# rat.net
KiCad netlist of a schematic drawn in EAGLE
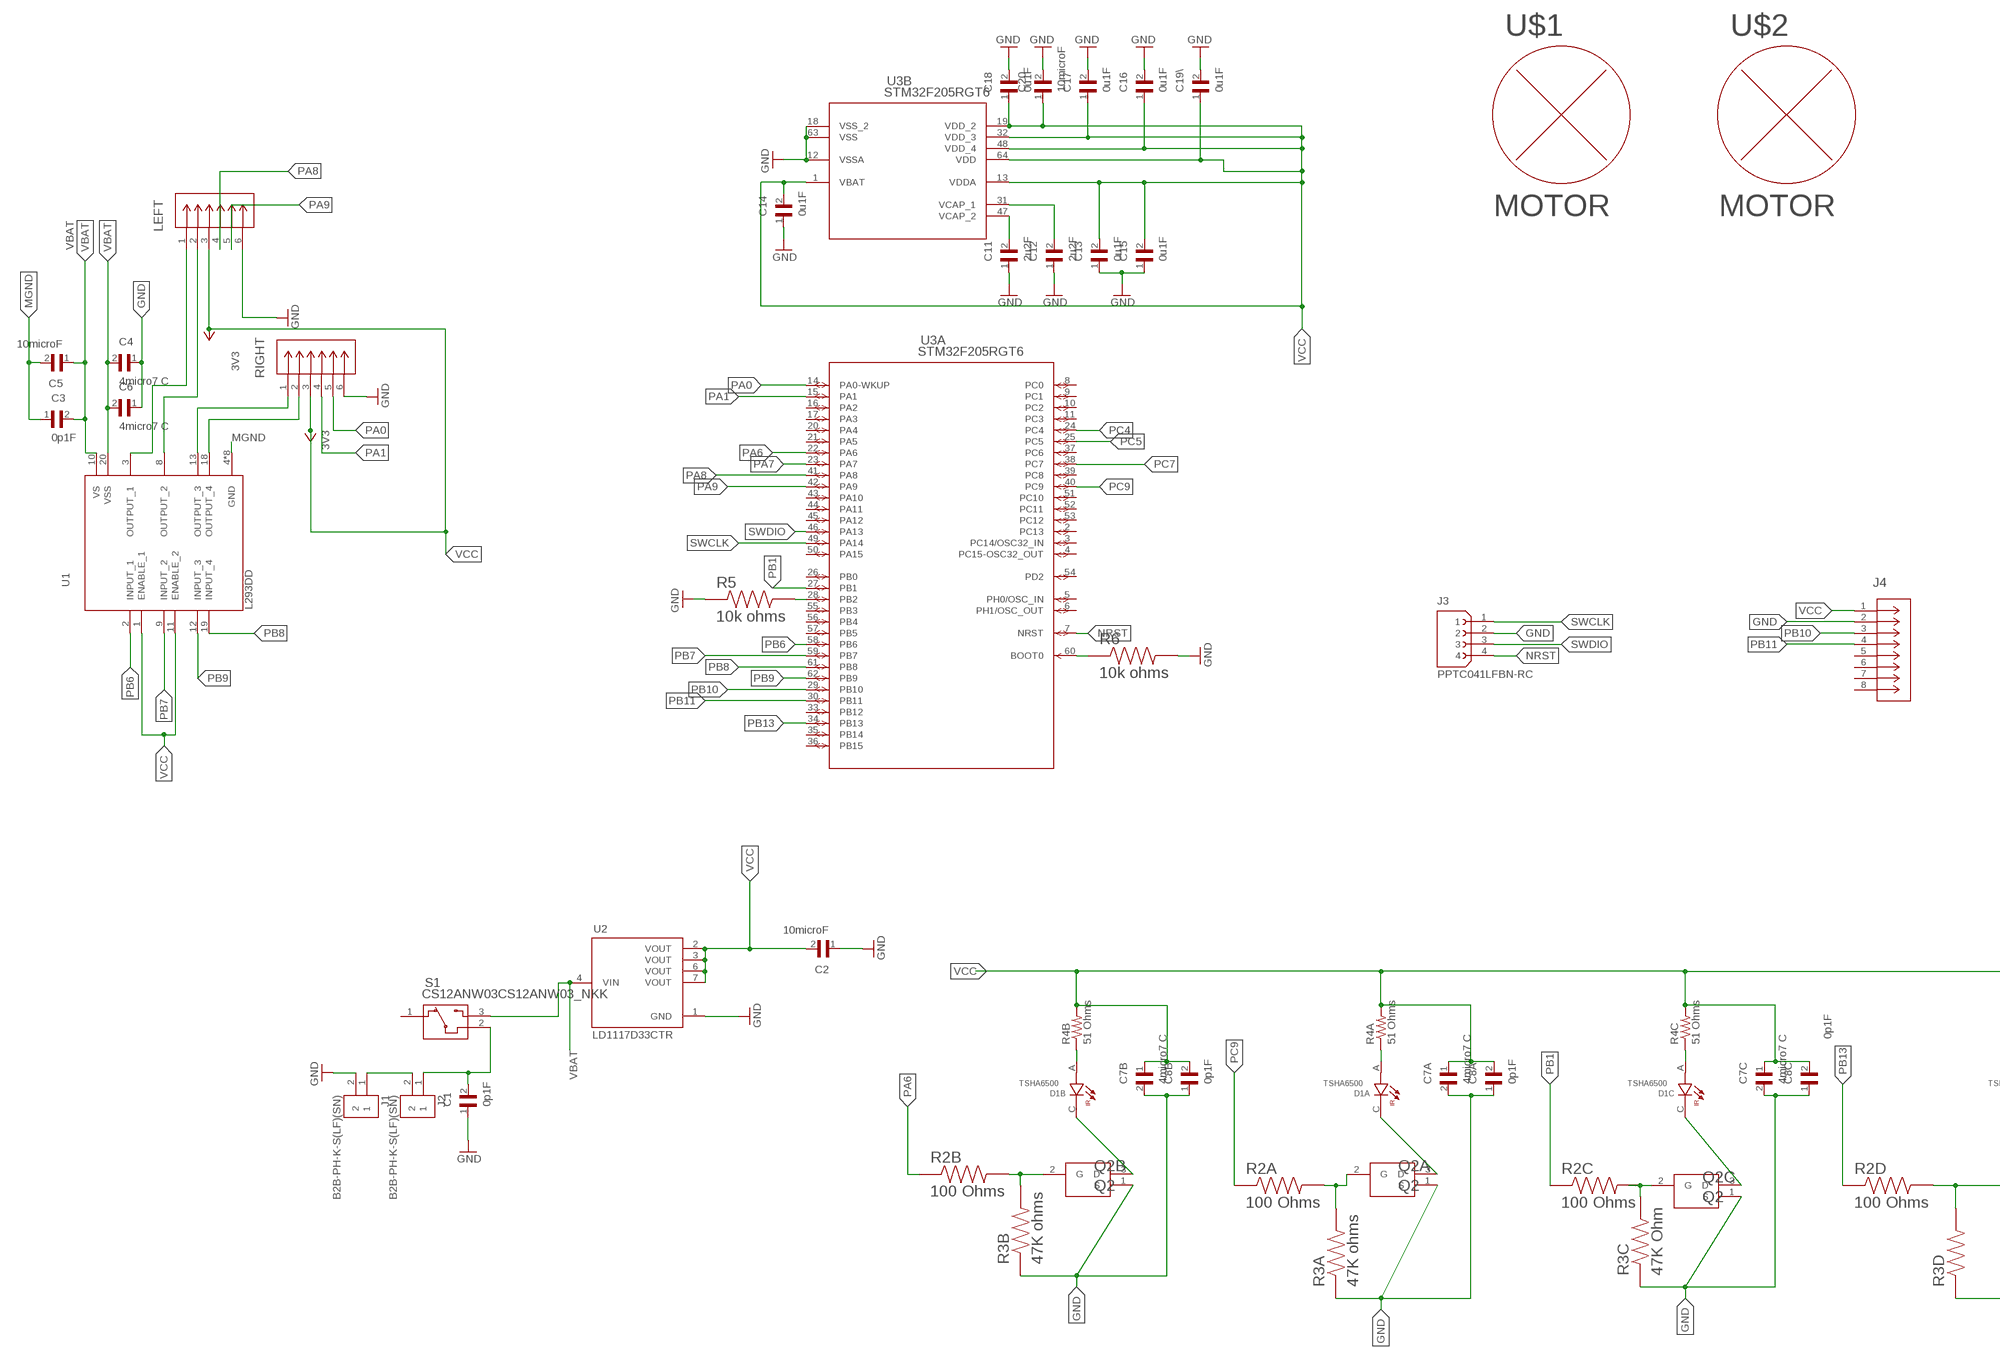
[diagram p0: schematic, sheet 1, part 1 of 2]
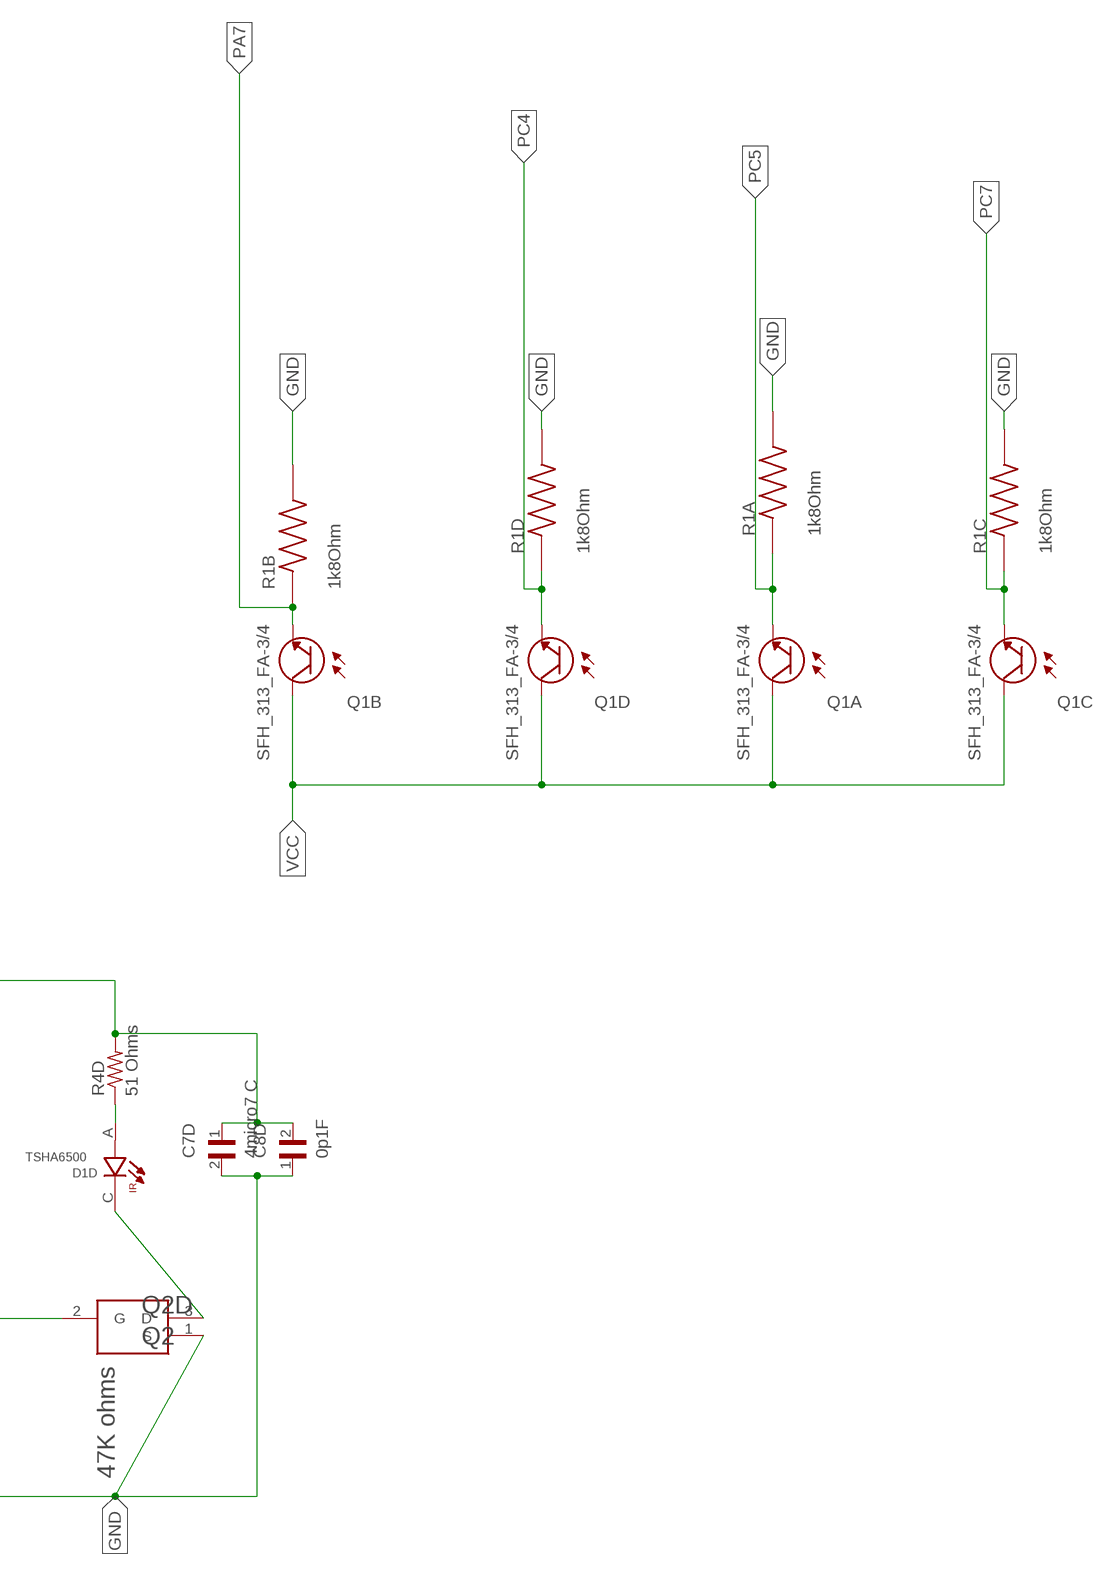
[diagram p1: schematic, sheet 1, part 2 of 2]

(export (version "E")
  (design (tool "Eeschema 10.0.6"))
  (components
    (comp (ref "C1")
      (value "0p1F")
      (footprint "eagle-import:CAPC3216X94N")
      (fields
        (field (name "DIGI-KEY_PART_NUMBER") "478-12514-1-ND")
        (field (name "MF") "AVX")
        (field (name "MP") "12065C104JAT4A")
      )
      (libsource (lib "eagle-import") (part "12065C104JAT4A"))
    )
    (comp (ref "C2")
      (value "10microF")
      (footprint "eagle-import:CAPC2012X145N")
      (fields
        (field (name "DIGI-KEY_PART_NUMBER") "445-175229-1-ND")
        (field (name "MF") "TDK")
        (field (name "MP") "C2012X7S1C106M125AC")
      )
      (libsource (lib "eagle-import") (part "C2012X7S1C106M125AC"))
    )
    (comp (ref "C3")
      (value "0p1F")
      (footprint "eagle-import:CAPC3216X94N")
      (fields
        (field (name "DIGI-KEY_PART_NUMBER") "478-12514-1-ND")
        (field (name "MF") "AVX")
        (field (name "MP") "12065C104JAT4A")
      )
      (libsource (lib "eagle-import") (part "12065C104JAT4A"))
    )
    (comp (ref "C4")
      (value "4micro7 C")
      (footprint "eagle-import:CAPC2012X140N")
      (fields
        (field (name "DIGI-KEY_PART_NUMBER") "1276-1244-1-ND")
        (field (name "MF") "Samsung Electro-Mechanics")
        (field (name "MP") "CL21A475KAQNNNE")
      )
      (libsource (lib "eagle-import") (part "CL21A475KAQNNNE"))
    )
    (comp (ref "C5")
      (value "10microF")
      (footprint "eagle-import:CAPC2012X145N")
      (fields
        (field (name "DIGI-KEY_PART_NUMBER") "445-175229-1-ND")
        (field (name "MF") "TDK")
        (field (name "MP") "C2012X7S1C106M125AC")
      )
      (libsource (lib "eagle-import") (part "C2012X7S1C106M125AC"))
    )
    (comp (ref "C6")
      (value "4micro7 C")
      (footprint "eagle-import:CAPC2012X140N")
      (fields
        (field (name "DIGI-KEY_PART_NUMBER") "1276-1244-1-ND")
        (field (name "MF") "Samsung Electro-Mechanics")
        (field (name "MP") "CL21A475KAQNNNE")
      )
      (libsource (lib "eagle-import") (part "CL21A475KAQNNNE"))
    )
    (comp (ref "C7A")
      (value "4micro7 C")
      (footprint "eagle-import:CAPC2012X140N")
      (fields
        (field (name "DIGI-KEY_PART_NUMBER") "1276-1244-1-ND")
        (field (name "MF") "Samsung Electro-Mechanics")
        (field (name "MP") "CL21A475KAQNNNE")
      )
      (libsource (lib "eagle-import") (part "CL21A475KAQNNNE"))
    )
    (comp (ref "C7B")
      (value "4micro7 C")
      (footprint "eagle-import:CAPC2012X140N")
      (fields
        (field (name "DIGI-KEY_PART_NUMBER") "1276-1244-1-ND")
        (field (name "MF") "Samsung Electro-Mechanics")
        (field (name "MP") "CL21A475KAQNNNE")
      )
      (libsource (lib "eagle-import") (part "CL21A475KAQNNNE"))
    )
    (comp (ref "C7C")
      (value "4micro7 C")
      (footprint "eagle-import:CAPC2012X140N")
      (fields
        (field (name "DIGI-KEY_PART_NUMBER") "1276-1244-1-ND")
        (field (name "MF") "Samsung Electro-Mechanics")
        (field (name "MP") "CL21A475KAQNNNE")
      )
      (libsource (lib "eagle-import") (part "CL21A475KAQNNNE"))
    )
    (comp (ref "C7D")
      (value "4micro7 C")
      (footprint "eagle-import:CAPC2012X140N")
      (fields
        (field (name "DIGI-KEY_PART_NUMBER") "1276-1244-1-ND")
        (field (name "MF") "Samsung Electro-Mechanics")
        (field (name "MP") "CL21A475KAQNNNE")
      )
      (libsource (lib "eagle-import") (part "CL21A475KAQNNNE"))
    )
    (comp (ref "C8A")
      (value "0p1F")
      (footprint "eagle-import:CAPC3216X94N")
      (fields
        (field (name "DIGI-KEY_PART_NUMBER") "478-12514-1-ND")
        (field (name "MF") "AVX")
        (field (name "MP") "12065C104JAT4A")
      )
      (libsource (lib "eagle-import") (part "12065C104JAT4A"))
    )
    (comp (ref "C8B")
      (value "0p1F")
      (footprint "eagle-import:CAPC3216X94N")
      (fields
        (field (name "DIGI-KEY_PART_NUMBER") "478-12514-1-ND")
        (field (name "MF") "AVX")
        (field (name "MP") "12065C104JAT4A")
      )
      (libsource (lib "eagle-import") (part "12065C104JAT4A"))
    )
    (comp (ref "C8C")
      (value "0p1F")
      (footprint "eagle-import:CAPC3216X94N")
      (fields
        (field (name "DIGI-KEY_PART_NUMBER") "478-12514-1-ND")
        (field (name "MF") "AVX")
        (field (name "MP") "12065C104JAT4A")
      )
      (libsource (lib "eagle-import") (part "12065C104JAT4A"))
    )
    (comp (ref "C8D")
      (value "0p1F")
      (footprint "eagle-import:CAPC3216X94N")
      (fields
        (field (name "DIGI-KEY_PART_NUMBER") "478-12514-1-ND")
        (field (name "MF") "AVX")
        (field (name "MP") "12065C104JAT4A")
      )
      (libsource (lib "eagle-import") (part "12065C104JAT4A"))
    )
    (comp (ref "C11")
      (value "2u2F")
      (footprint "eagle-import:CAPC3216X140N")
      (fields
        (field (name "DIGI-KEY_PART_NUMBER") "1276-2723-1-ND")
        (field (name "MF") "Samsung Electro-Mechanics")
        (field (name "MP") "CL31A225KB9LNNC")
      )
      (libsource (lib "eagle-import") (part "CL31A225KB9LNNC"))
    )
    (comp (ref "C12")
      (value "2u2F")
      (footprint "eagle-import:CAPC3216X140N")
      (fields
        (field (name "DIGI-KEY_PART_NUMBER") "1276-2723-1-ND")
        (field (name "MF") "Samsung Electro-Mechanics")
        (field (name "MP") "CL31A225KB9LNNC")
      )
      (libsource (lib "eagle-import") (part "CL31A225KB9LNNC"))
    )
    (comp (ref "C13")
      (value "0u1F")
      (footprint "eagle-import:CAPC3216X94N")
      (fields
        (field (name "DIGI-KEY_PART_NUMBER") "478-12514-1-ND")
        (field (name "MF") "AVX")
        (field (name "MP") "12065C104JAT4A")
      )
      (libsource (lib "eagle-import") (part "12065C104JAT4A"))
    )
    (comp (ref "C14")
      (value "0u1F")
      (footprint "eagle-import:CAPC3216X94N")
      (fields
        (field (name "DIGI-KEY_PART_NUMBER") "478-12514-1-ND")
        (field (name "MF") "AVX")
        (field (name "MP") "12065C104JAT4A")
      )
      (libsource (lib "eagle-import") (part "12065C104JAT4A"))
    )
    (comp (ref "C15")
      (value "0u1F")
      (footprint "eagle-import:CAPC3216X94N")
      (fields
        (field (name "DIGI-KEY_PART_NUMBER") "478-12514-1-ND")
        (field (name "MF") "AVX")
        (field (name "MP") "12065C104JAT4A")
      )
      (libsource (lib "eagle-import") (part "12065C104JAT4A"))
    )
    (comp (ref "C16")
      (value "0u1F")
      (footprint "eagle-import:CAPC3216X94N")
      (fields
        (field (name "DIGI-KEY_PART_NUMBER") "478-12514-1-ND")
        (field (name "MF") "AVX")
        (field (name "MP") "12065C104JAT4A")
      )
      (libsource (lib "eagle-import") (part "12065C104JAT4A"))
    )
    (comp (ref "C17")
      (value "0u1F")
      (footprint "eagle-import:CAPC3216X94N")
      (fields
        (field (name "DIGI-KEY_PART_NUMBER") "478-12514-1-ND")
        (field (name "MF") "AVX")
        (field (name "MP") "12065C104JAT4A")
      )
      (libsource (lib "eagle-import") (part "12065C104JAT4A"))
    )
    (comp (ref "C18")
      (value "0u1F")
      (footprint "eagle-import:CAPC3216X94N")
      (fields
        (field (name "DIGI-KEY_PART_NUMBER") "478-12514-1-ND")
        (field (name "MF") "AVX")
        (field (name "MP") "12065C104JAT4A")
      )
      (libsource (lib "eagle-import") (part "12065C104JAT4A"))
    )
    (comp (ref "C19\\")
      (value "0u1F")
      (footprint "eagle-import:CAPC3216X94N")
      (fields
        (field (name "DIGI-KEY_PART_NUMBER") "478-12514-1-ND")
        (field (name "MF") "AVX")
        (field (name "MP") "12065C104JAT4A")
      )
      (libsource (lib "eagle-import") (part "12065C104JAT4A"))
    )
    (comp (ref "C20")
      (value "10microF")
      (footprint "eagle-import:CAPC2012X145N")
      (fields
        (field (name "DIGI-KEY_PART_NUMBER") "445-175229-1-ND")
        (field (name "MF") "TDK")
        (field (name "MP") "C2012X7S1C106M125AC")
      )
      (libsource (lib "eagle-import") (part "C2012X7S1C106M125AC"))
    )
    (comp (ref "D1A")
      (value "TSHA6500")
      (footprint "eagle-import:LEDRD254W55D595H900")
      (fields (field (name "MF") "Vishay"))
      (libsource (lib "eagle-import") (part "TSHA6500"))
    )
    (comp (ref "D1B")
      (value "TSHA6500")
      (footprint "eagle-import:LEDRD254W55D595H900")
      (fields (field (name "MF") "Vishay"))
      (libsource (lib "eagle-import") (part "TSHA6500"))
    )
    (comp (ref "D1C")
      (value "TSHA6500")
      (footprint "eagle-import:LEDRD254W55D595H900")
      (fields (field (name "MF") "Vishay"))
      (libsource (lib "eagle-import") (part "TSHA6500"))
    )
    (comp (ref "D1D")
      (value "TSHA6500")
      (footprint "eagle-import:LEDRD254W55D595H900")
      (fields (field (name "MF") "Vishay"))
      (libsource (lib "eagle-import") (part "TSHA6500"))
    )
    (comp (ref "J1")
      (value "B2B-PH-K-S(LF)(SN)")
      (footprint "eagle-import:JST_B2B-PH-K-S(LF)(SN)")
      (fields (field (name "DIGI-KEY_PART_NUMBER") "455-1704-ND") (field (name "MF") "JST Sales"))
      (libsource (lib "eagle-import") (part "B2B-PH-K-S(LF)(SN)"))
    )
    (comp (ref "J2")
      (value "B2B-PH-K-S(LF)(SN)")
      (footprint "eagle-import:JST_B2B-PH-K-S(LF)(SN)")
      (fields (field (name "DIGI-KEY_PART_NUMBER") "455-1704-ND") (field (name "MF") "JST Sales"))
      (libsource (lib "eagle-import") (part "B2B-PH-K-S(LF)(SN)"))
    )
    (comp (ref "J3")
      (value "PPTC041LFBN-RC")
      (footprint "eagle-import:SULLINS_PPTC041LFBN-RC")
      (fields (field (name "DIGI-KEY_PART_NUMBER") "S7002-ND") (field (name "MF") "Sullins Connector"))
      (libsource (lib "eagle-import") (part "PPTC041LFBN-RC"))
    )
    (comp (ref "J4")
      (value "PPTC081LFBN-RCCONN_PPTC081LFBN-RC_SUL")
      (footprint "eagle-import:CONN_PPTC081LFBN-RC_SUL")
      (fields
        (field (name "MANUFACTURER_PART_NUMBER") "PPTC081LFBN-RC")
        (field (name "COPYRIGHT") "Copyright (C) 2022 Ultra Librarian. All rights reserved.")
      )
      (libsource (lib "eagle-import") (part "PPTC081LFBN-RCCONN_PPTC081LFBN-RC_SUL"))
    )
    (comp (ref "LEFT")
      (value "PPTC061LFBN-RCCONN6_061LFBN-RC_SUL")
      (footprint "eagle-import:CONN6_061LFBN-RC_SUL")
      (fields
        (field (name "MANUFACTURER_PART_NUMBER") "PPTC061LFBN-RC")
        (field (name "COPYRIGHT") "Copyright (C) 2022 Ultra Librarian. All rights reserved.")
      )
      (libsource (lib "eagle-import") (part "PPTC061LFBN-RCCONN6_061LFBN-RC_SUL"))
    )
    (comp (ref "Q1A")
      (value "SFH_313_FA-3/4")
      (footprint "eagle-import:XDCR_SFH_313_FA-3_4")
      (fields (field (name "MF") "OSRAM Opto") (field (name "MP") "SFH 313 FA-3/4"))
      (libsource (lib "eagle-import") (part "SFH_313_FA-3/4"))
    )
    (comp (ref "Q1B")
      (value "SFH_313_FA-3/4")
      (footprint "eagle-import:XDCR_SFH_313_FA-3_4")
      (fields (field (name "MF") "OSRAM Opto") (field (name "MP") "SFH 313 FA-3/4"))
      (libsource (lib "eagle-import") (part "SFH_313_FA-3/4"))
    )
    (comp (ref "Q1C")
      (value "SFH_313_FA-3/4")
      (footprint "eagle-import:XDCR_SFH_313_FA-3_4")
      (fields (field (name "MF") "OSRAM Opto") (field (name "MP") "SFH 313 FA-3/4"))
      (libsource (lib "eagle-import") (part "SFH_313_FA-3/4"))
    )
    (comp (ref "Q1D")
      (value "SFH_313_FA-3/4")
      (footprint "eagle-import:XDCR_SFH_313_FA-3_4")
      (fields (field (name "MF") "OSRAM Opto") (field (name "MP") "SFH 313 FA-3/4"))
      (libsource (lib "eagle-import") (part "SFH_313_FA-3/4"))
    )
    (comp (ref "Q2A")
      (value "Q2")
      (footprint "eagle-import:PF5102")
      (fields
        (field (name "ARROW_PART_NUMBER") "2N7000_D26Z")
        (field (name "MOUSER_PART_NUMBER") "512-2N7000D26Z")
      )
      (libsource (lib "eagle-import") (part "2N7000_D26Z"))
    )
    (comp (ref "Q2B")
      (value "Q2")
      (footprint "eagle-import:PF5102")
      (fields
        (field (name "ARROW_PART_NUMBER") "2N7000_D26Z")
        (field (name "MOUSER_PART_NUMBER") "512-2N7000D26Z")
      )
      (libsource (lib "eagle-import") (part "2N7000_D26Z"))
    )
    (comp (ref "Q2C")
      (value "Q2")
      (footprint "eagle-import:PF5102")
      (fields
        (field (name "ARROW_PART_NUMBER") "2N7000_D26Z")
        (field (name "MOUSER_PART_NUMBER") "512-2N7000D26Z")
      )
      (libsource (lib "eagle-import") (part "2N7000_D26Z"))
    )
    (comp (ref "Q2D")
      (value "Q2")
      (footprint "eagle-import:PF5102")
      (fields
        (field (name "ARROW_PART_NUMBER") "2N7000_D26Z")
        (field (name "MOUSER_PART_NUMBER") "512-2N7000D26Z")
      )
      (libsource (lib "eagle-import") (part "2N7000_D26Z"))
    )
    (comp (ref "R1A")
      (value "1k8Ohm")
      (footprint "eagle-import:RES_ERJH3EF1801V")
      (fields
        (field (name "DIGI-KEY_PART_NUMBER") "10-ERJ-H3EF1801VCT-ND")
        (field (name "MF") "Panasonic")
        (field (name "MP") "ERJH3EF1801V")
      )
      (libsource (lib "eagle-import") (part "ERJH3EF1801V"))
    )
    (comp (ref "R1B")
      (value "1k8Ohm")
      (footprint "eagle-import:RES_ERJH3EF1801V")
      (fields
        (field (name "DIGI-KEY_PART_NUMBER") "10-ERJ-H3EF1801VCT-ND")
        (field (name "MF") "Panasonic")
        (field (name "MP") "ERJH3EF1801V")
      )
      (libsource (lib "eagle-import") (part "ERJH3EF1801V"))
    )
    (comp (ref "R1C")
      (value "1k8Ohm")
      (footprint "eagle-import:RES_ERJH3EF1801V")
      (fields
        (field (name "DIGI-KEY_PART_NUMBER") "10-ERJ-H3EF1801VCT-ND")
        (field (name "MF") "Panasonic")
        (field (name "MP") "ERJH3EF1801V")
      )
      (libsource (lib "eagle-import") (part "ERJH3EF1801V"))
    )
    (comp (ref "R1D")
      (value "1k8Ohm")
      (footprint "eagle-import:RES_ERJH3EF1801V")
      (fields
        (field (name "DIGI-KEY_PART_NUMBER") "10-ERJ-H3EF1801VCT-ND")
        (field (name "MF") "Panasonic")
        (field (name "MP") "ERJH3EF1801V")
      )
      (libsource (lib "eagle-import") (part "ERJH3EF1801V"))
    )
    (comp (ref "R2A")
      (value "100 Ohms")
      (footprint "eagle-import:RESC2012X50N")
      (fields
        (field (name "DIGI-KEY_PART_NUMBER") "RG20P100BCT-ND")
        (field (name "MF") "Susumu")
        (field (name "MP") "RG2012P-101-B-T5")
      )
      (libsource (lib "eagle-import") (part "RG2012P-101-B-T5"))
    )
    (comp (ref "R2B")
      (value "100 Ohms")
      (footprint "eagle-import:RESC2012X50N")
      (fields
        (field (name "DIGI-KEY_PART_NUMBER") "RG20P100BCT-ND")
        (field (name "MF") "Susumu")
        (field (name "MP") "RG2012P-101-B-T5")
      )
      (libsource (lib "eagle-import") (part "RG2012P-101-B-T5"))
    )
    (comp (ref "R2C")
      (value "100 Ohms")
      (footprint "eagle-import:RESC2012X50N")
      (fields
        (field (name "DIGI-KEY_PART_NUMBER") "RG20P100BCT-ND")
        (field (name "MF") "Susumu")
        (field (name "MP") "RG2012P-101-B-T5")
      )
      (libsource (lib "eagle-import") (part "RG2012P-101-B-T5"))
    )
    (comp (ref "R2D")
      (value "100 Ohms")
      (footprint "eagle-import:RESC2012X50N")
      (fields
        (field (name "DIGI-KEY_PART_NUMBER") "RG20P100BCT-ND")
        (field (name "MF") "Susumu")
        (field (name "MP") "RG2012P-101-B-T5")
      )
      (libsource (lib "eagle-import") (part "RG2012P-101-B-T5"))
    )
    (comp (ref "R3A")
      (value "47K ohms")
      (footprint "eagle-import:RESC1005X40N")
      (fields
        (field (name "COMMENT") "2-2176338-9")
        (field (name "MF") "TE Connectivity")
        (field (name "MP") "CRGCQ0402J47K")
      )
      (libsource (lib "eagle-import") (part "CRGCQ0402J47K"))
    )
    (comp (ref "R3B")
      (value "47K ohms")
      (footprint "eagle-import:RESC1005X40N")
      (fields
        (field (name "COMMENT") "2-2176338-9")
        (field (name "MF") "TE Connectivity")
        (field (name "MP") "CRGCQ0402J47K")
      )
      (libsource (lib "eagle-import") (part "CRGCQ0402J47K"))
    )
    (comp (ref "R3C")
      (value "47K Ohm")
      (footprint "eagle-import:RESC1005X40N")
      (fields
        (field (name "COMMENT") "2-2176338-9")
        (field (name "MF") "TE Connectivity")
        (field (name "MP") "CRGCQ0402J47K")
      )
      (libsource (lib "eagle-import") (part "CRGCQ0402J47K"))
    )
    (comp (ref "R3D")
      (value "47K ohms")
      (footprint "eagle-import:RESC1005X40N")
      (fields
        (field (name "COMMENT") "2-2176338-9")
        (field (name "MF") "TE Connectivity")
        (field (name "MP") "CRGCQ0402J47K")
      )
      (libsource (lib "eagle-import") (part "CRGCQ0402J47K"))
    )
    (comp (ref "R4A")
      (value "51 Ohms")
      (footprint "eagle-import:RESC2012X65N")
      (fields
        (field (name "COMMENT") "1623246-1")
        (field (name "DIGI-KEY_PART_NUMBER") "A126374CT-ND")
        (field (name "MF") "TE Connectivity")
      )
      (libsource (lib "eagle-import") (part "1623246-1"))
    )
    (comp (ref "R4B")
      (value "51 Ohms")
      (footprint "eagle-import:RESC2012X65N")
      (fields
        (field (name "COMMENT") "1623246-1")
        (field (name "DIGI-KEY_PART_NUMBER") "A126374CT-ND")
        (field (name "MF") "TE Connectivity")
      )
      (libsource (lib "eagle-import") (part "1623246-1"))
    )
    (comp (ref "R4C")
      (value "51 Ohms")
      (footprint "eagle-import:RESC2012X65N")
      (fields
        (field (name "COMMENT") "1623246-1")
        (field (name "DIGI-KEY_PART_NUMBER") "A126374CT-ND")
        (field (name "MF") "TE Connectivity")
      )
      (libsource (lib "eagle-import") (part "1623246-1"))
    )
    (comp (ref "R4D")
      (value "51 Ohms")
      (footprint "eagle-import:RESC2012X65N")
      (fields
        (field (name "COMMENT") "1623246-1")
        (field (name "DIGI-KEY_PART_NUMBER") "A126374CT-ND")
        (field (name "MF") "TE Connectivity")
      )
      (libsource (lib "eagle-import") (part "1623246-1"))
    )
    (comp (ref "R5")
      (value "10k ohms")
      (footprint "eagle-import:RESC2012X65N")
      (fields
        (field (name "COMMENT") "1676153-3")
        (field (name "MF") "TE Connectivity")
        (field (name "MP") "RN73C2A10KBTD")
      )
      (libsource (lib "eagle-import") (part "RN73C2A10KBTD"))
    )
    (comp (ref "R6")
      (value "10k ohms")
      (footprint "eagle-import:RESC2012X65N")
      (fields
        (field (name "COMMENT") "1676153-3")
        (field (name "MF") "TE Connectivity")
        (field (name "MP") "RN73C2A10KBTD")
      )
      (libsource (lib "eagle-import") (part "RN73C2A10KBTD"))
    )
    (comp (ref "RIGHT")
      (value "PPTC061LFBN-RCCONN6_061LFBN-RC_SUL")
      (footprint "eagle-import:CONN6_061LFBN-RC_SUL")
      (fields
        (field (name "MANUFACTURER_PART_NUMBER") "PPTC061LFBN-RC")
        (field (name "COPYRIGHT") "Copyright (C) 2022 Ultra Librarian. All rights reserved.")
      )
      (libsource (lib "eagle-import") (part "PPTC061LFBN-RCCONN6_061LFBN-RC_SUL"))
    )
    (comp (ref "S1")
      (value "CS12ANW03CS12ANW03_NKK")
      (footprint "eagle-import:CS12ANW03_NKK")
      (fields
        (field (name "MANUFACTURER_PART_NUMBER") "CS12ANW03")
        (field (name "COPYRIGHT") "Copyright (C) 2022 Ultra Librarian. All rights reserved.")
      )
      (libsource (lib "eagle-import") (part "CS12ANW03CS12ANW03_NKK"))
    )
    (comp (ref "U$1")
      (value "MOTOR")
      (footprint "eagle-import:MOTOR")
      (libsource (lib "eagle-import") (part "MOTOR"))
    )
    (comp (ref "U$2")
      (value "MOTOR")
      (footprint "eagle-import:MOTOR")
      (libsource (lib "eagle-import") (part "MOTOR"))
    )
    (comp (ref "U1")
      (value "L293DD")
      (footprint "eagle-import:SOIC127P1032X265-20N")
      (fields (field (name "DIGI-KEY_PART_NUMBER") "497-2937-2-ND") (field (name "MF") "STMicroelectronics"))
      (libsource (lib "eagle-import") (part "L293DD"))
    )
    (comp (ref "U2")
      (value "LD1117D33CTR")
      (footprint "eagle-import:SOIC127P600X175-8N")
      (fields (field (name "DIGI-KEY_PART_NUMBER") "497-1230-1-ND") (field (name "MF") "STMicroelectronics"))
      (libsource (lib "eagle-import") (part "LD1117D33CTR"))
    )
    (comp (ref "U3")
      (value "STM32F205RGT6")
      (footprint "eagle-import:LQFP64-10X10MM")
      (fields (field (name "COPYRIGHT") "Copyright (C) 2021 Ultra Librarian. All rights reserved."))
      (libsource (lib "eagle-import") (part "STM32F205RGT6"))
    )
  )
  (nets
    (net (code "1") (name "GND") (class "Default")
      (node (ref "C1") (pin "1") (pinfunction "1_1") (pintype "passive"))
      (node (ref "C11") (pin "1") (pinfunction "1_1") (pintype "passive"))
      (node (ref "C12") (pin "1") (pinfunction "1_1") (pintype "passive"))
      (node (ref "C13") (pin "1") (pinfunction "1_1") (pintype "passive"))
      (node (ref "C14") (pin "1") (pinfunction "1_1") (pintype "passive"))
      (node (ref "C15") (pin "1") (pinfunction "1_1") (pintype "passive"))
      (node (ref "C16") (pin "2") (pinfunction "2_2") (pintype "passive"))
      (node (ref "C17") (pin "2") (pinfunction "2_2") (pintype "passive"))
      (node (ref "C18") (pin "2") (pinfunction "2_2") (pintype "passive"))
      (node (ref "C19\\") (pin "2") (pinfunction "2_2") (pintype "passive"))
      (node (ref "C2") (pin "1") (pinfunction "1_1") (pintype "passive"))
      (node (ref "C20") (pin "2") (pinfunction "2_2") (pintype "passive"))
      (node (ref "C4") (pin "1") (pinfunction "1_1") (pintype "passive"))
      (node (ref "C6") (pin "1") (pinfunction "1_1") (pintype "passive"))
      (node (ref "C7A") (pin "2") (pinfunction "2_2") (pintype "passive"))
      (node (ref "C7B") (pin "2") (pinfunction "2_2") (pintype "passive"))
      (node (ref "C7C") (pin "2") (pinfunction "2_2") (pintype "passive"))
      (node (ref "C7D") (pin "2") (pinfunction "2_2") (pintype "passive"))
      (node (ref "C8A") (pin "1") (pinfunction "1_1") (pintype "passive"))
      (node (ref "C8B") (pin "1") (pinfunction "1_1") (pintype "passive"))
      (node (ref "C8C") (pin "1") (pinfunction "1_1") (pintype "passive"))
      (node (ref "C8D") (pin "1") (pinfunction "1_1") (pintype "passive"))
      (node (ref "J1") (pin "2") (pinfunction "2_2") (pintype "passive"))
      (node (ref "J3") (pin "2") (pinfunction "2_2") (pintype "passive"))
      (node (ref "J4") (pin "2") (pinfunction "2_2") (pintype "passive"))
      (node (ref "LEFT") (pin "6") (pinfunction "6_6") (pintype "passive"))
      (node (ref "Q2A") (pin "1") (pinfunction "S_1") (pintype "bidirectional"))
      (node (ref "Q2B") (pin "1") (pinfunction "S_1") (pintype "bidirectional"))
      (node (ref "Q2C") (pin "1") (pinfunction "S_1") (pintype "bidirectional"))
      (node (ref "Q2D") (pin "1") (pinfunction "S_1") (pintype "bidirectional"))
      (node (ref "R1A") (pin "2") (pinfunction "2_2") (pintype "passive"))
      (node (ref "R1B") (pin "2") (pinfunction "2_2") (pintype "passive"))
      (node (ref "R1C") (pin "2") (pinfunction "2_2") (pintype "passive"))
      (node (ref "R1D") (pin "2") (pinfunction "2_2") (pintype "passive"))
      (node (ref "R3A") (pin "1") (pinfunction "1_1") (pintype "passive"))
      (node (ref "R3B") (pin "1") (pinfunction "1_1") (pintype "passive"))
      (node (ref "R3C") (pin "1") (pinfunction "1_1") (pintype "passive"))
      (node (ref "R3D") (pin "1") (pinfunction "1_1") (pintype "passive"))
      (node (ref "R5") (pin "1") (pinfunction "1_1") (pintype "passive"))
      (node (ref "R6") (pin "2") (pinfunction "2_2") (pintype "passive"))
      (node (ref "RIGHT") (pin "6") (pinfunction "6_6") (pintype "passive"))
      (node (ref "U2") (pin "1") (pinfunction "GND_1") (pintype "power_in"))
      (node (ref "U3") (pin "12") (pinfunction "VSSA_12") (pintype "power_in"))
      (node (ref "U3") (pin "18") (pinfunction "VSS_2_18") (pintype "power_in"))
      (node (ref "U3") (pin "63") (pinfunction "VSS_63") (pintype "power_in"))
    )
    (net (code "2") (name "MGND") (class "Default")
      (node (ref "C3") (pin "1") (pinfunction "1_1") (pintype "passive"))
      (node (ref "C5") (pin "2") (pinfunction "2_2") (pintype "passive"))
      (node (ref "U1") (pin "14") (pinfunction "GND_14") (pintype "power_in"))
      (node (ref "U1") (pin "15") (pinfunction "GND_15") (pintype "power_in"))
      (node (ref "U1") (pin "16") (pinfunction "GND_16") (pintype "power_in"))
      (node (ref "U1") (pin "17") (pinfunction "GND_17") (pintype "power_in"))
      (node (ref "U1") (pin "4") (pinfunction "GND_4") (pintype "power_in"))
      (node (ref "U1") (pin "5") (pinfunction "GND_5") (pintype "power_in"))
      (node (ref "U1") (pin "6") (pinfunction "GND_6") (pintype "power_in"))
      (node (ref "U1") (pin "7") (pinfunction "GND_7") (pintype "power_in"))
    )
    (net (code "3") (name "NRST") (class "Default")
      (node (ref "J3") (pin "4") (pinfunction "4_4") (pintype "passive"))
      (node (ref "U3") (pin "7") (pinfunction "NRST_7") (pintype "bidirectional"))
    )
    (net (code "4") (name "Net-(C1-Pad2)") (class "Default")
      (node (ref "C1") (pin "2") (pinfunction "2_2") (pintype "passive"))
      (node (ref "J2") (pin "1") (pinfunction "1_1") (pintype "passive"))
      (node (ref "S1") (pin "2") (pinfunction "2_2") (pintype "passive"))
    )
    (net (code "5") (name "Net-(D1A-PadA)") (class "Default")
      (node (ref "D1A") (pin "A") (pinfunction "A_A") (pintype "passive"))
      (node (ref "R4A") (pin "1") (pinfunction "1_1") (pintype "passive"))
    )
    (net (code "6") (name "Net-(D1B-PadA)") (class "Default")
      (node (ref "D1B") (pin "A") (pinfunction "A_A") (pintype "passive"))
      (node (ref "R4B") (pin "1") (pinfunction "1_1") (pintype "passive"))
    )
    (net (code "7") (name "Net-(D1C-PadA)") (class "Default")
      (node (ref "D1C") (pin "A") (pinfunction "A_A") (pintype "passive"))
      (node (ref "R4C") (pin "1") (pinfunction "1_1") (pintype "passive"))
    )
    (net (code "8") (name "Net-(D1D-PadA)") (class "Default")
      (node (ref "D1D") (pin "A") (pinfunction "A_A") (pintype "passive"))
      (node (ref "R4D") (pin "1") (pinfunction "1_1") (pintype "passive"))
    )
    (net (code "9") (name "Net-(J1-Pad1)") (class "Default")
      (node (ref "J1") (pin "1") (pinfunction "1_1") (pintype "passive"))
      (node (ref "J2") (pin "2") (pinfunction "2_2") (pintype "passive"))
    )
    (net (code "10") (name "Net-(Q2A-D)") (class "Default")
      (node (ref "D1A") (pin "C") (pinfunction "C_C") (pintype "passive"))
      (node (ref "Q2A") (pin "3") (pinfunction "D_3") (pintype "bidirectional"))
    )
    (net (code "11") (name "Net-(Q2A-G)") (class "Default")
      (node (ref "Q2A") (pin "2") (pinfunction "G_2") (pintype "bidirectional"))
      (node (ref "R2A") (pin "2") (pinfunction "2_2") (pintype "passive"))
      (node (ref "R3A") (pin "2") (pinfunction "2_2") (pintype "passive"))
    )
    (net (code "12") (name "Net-(Q2B-D)") (class "Default")
      (node (ref "D1B") (pin "C") (pinfunction "C_C") (pintype "passive"))
      (node (ref "Q2B") (pin "3") (pinfunction "D_3") (pintype "bidirectional"))
    )
    (net (code "13") (name "Net-(Q2B-G)") (class "Default")
      (node (ref "Q2B") (pin "2") (pinfunction "G_2") (pintype "bidirectional"))
      (node (ref "R2B") (pin "2") (pinfunction "2_2") (pintype "passive"))
      (node (ref "R3B") (pin "2") (pinfunction "2_2") (pintype "passive"))
    )
    (net (code "14") (name "Net-(Q2C-D)") (class "Default")
      (node (ref "D1C") (pin "C") (pinfunction "C_C") (pintype "passive"))
      (node (ref "Q2C") (pin "3") (pinfunction "D_3") (pintype "bidirectional"))
    )
    (net (code "15") (name "Net-(Q2C-G)") (class "Default")
      (node (ref "Q2C") (pin "2") (pinfunction "G_2") (pintype "bidirectional"))
      (node (ref "R2C") (pin "2") (pinfunction "2_2") (pintype "passive"))
      (node (ref "R3C") (pin "2") (pinfunction "2_2") (pintype "passive"))
    )
    (net (code "16") (name "Net-(Q2D-D)") (class "Default")
      (node (ref "D1D") (pin "C") (pinfunction "C_C") (pintype "passive"))
      (node (ref "Q2D") (pin "3") (pinfunction "D_3") (pintype "bidirectional"))
    )
    (net (code "17") (name "Net-(Q2D-G)") (class "Default")
      (node (ref "Q2D") (pin "2") (pinfunction "G_2") (pintype "bidirectional"))
      (node (ref "R2D") (pin "2") (pinfunction "2_2") (pintype "passive"))
      (node (ref "R3D") (pin "2") (pinfunction "2_2") (pintype "passive"))
    )
    (net (code "18") (name "Net-(U1-OUTPUT_1)") (class "Default")
      (node (ref "LEFT") (pin "1") (pinfunction "1_1") (pintype "passive"))
      (node (ref "U1") (pin "3") (pinfunction "OUTPUT_1_3") (pintype "output"))
    )
    (net (code "19") (name "Net-(U1-OUTPUT_2)") (class "Default")
      (node (ref "LEFT") (pin "2") (pinfunction "2_2") (pintype "passive"))
      (node (ref "U1") (pin "8") (pinfunction "OUTPUT_2_8") (pintype "output"))
    )
    (net (code "20") (name "Net-(U1-OUTPUT_3)") (class "Default")
      (node (ref "RIGHT") (pin "1") (pinfunction "1_1") (pintype "passive"))
      (node (ref "U1") (pin "13") (pinfunction "OUTPUT_3_13") (pintype "output"))
    )
    (net (code "21") (name "Net-(U1-OUTPUT_4)") (class "Default")
      (node (ref "RIGHT") (pin "2") (pinfunction "2_2") (pintype "passive"))
      (node (ref "U1") (pin "18") (pinfunction "OUTPUT_4_18") (pintype "output"))
    )
    (net (code "22") (name "Net-(U3A-BOOT0)") (class "Default")
      (node (ref "R6") (pin "1") (pinfunction "1_1") (pintype "passive"))
      (node (ref "U3") (pin "60") (pinfunction "BOOT0_60") (pintype "input"))
    )
    (net (code "23") (name "Net-(U3A-PB2)") (class "Default")
      (node (ref "R5") (pin "2") (pinfunction "2_2") (pintype "passive"))
      (node (ref "U3") (pin "28") (pinfunction "PB2_28") (pintype "bidirectional"))
    )
    (net (code "24") (name "Net-(U3B-VCAP_1)") (class "Default")
      (node (ref "C12") (pin "2") (pinfunction "2_2") (pintype "passive"))
      (node (ref "U3") (pin "31") (pinfunction "VCAP_1_31") (pintype "power_in"))
    )
    (net (code "25") (name "Net-(U3B-VCAP_2)") (class "Default")
      (node (ref "C11") (pin "2") (pinfunction "2_2") (pintype "passive"))
      (node (ref "U3") (pin "47") (pinfunction "VCAP_2_47") (pintype "power_in"))
    )
    (net (code "26") (name "PA0") (class "Default")
      (node (ref "RIGHT") (pin "5") (pinfunction "5_5") (pintype "passive"))
      (node (ref "U3") (pin "14") (pinfunction "PA0-WKUP_14") (pintype "bidirectional"))
    )
    (net (code "27") (name "PA1") (class "Default")
      (node (ref "RIGHT") (pin "4") (pinfunction "4_4") (pintype "passive"))
      (node (ref "U3") (pin "15") (pinfunction "PA1_15") (pintype "bidirectional"))
    )
    (net (code "28") (name "PA6") (class "Default")
      (node (ref "R2B") (pin "1") (pinfunction "1_1") (pintype "passive"))
      (node (ref "U3") (pin "22") (pinfunction "PA6_22") (pintype "bidirectional"))
    )
    (net (code "29") (name "PA7") (class "Default")
      (node (ref "Q1B") (pin "1") (pinfunction "E_1") (pintype "passive"))
      (node (ref "R1B") (pin "1") (pinfunction "1_1") (pintype "passive"))
      (node (ref "U3") (pin "23") (pinfunction "PA7_23") (pintype "bidirectional"))
    )
    (net (code "30") (name "PA8") (class "Default")
      (node (ref "LEFT") (pin "4") (pinfunction "4_4") (pintype "passive"))
      (node (ref "U3") (pin "41") (pinfunction "PA8_41") (pintype "bidirectional"))
    )
    (net (code "31") (name "PA9") (class "Default")
      (node (ref "LEFT") (pin "5") (pinfunction "5_5") (pintype "passive"))
      (node (ref "U3") (pin "42") (pinfunction "PA9_42") (pintype "bidirectional"))
    )
    (net (code "32") (name "PB1") (class "Default")
      (node (ref "R2C") (pin "1") (pinfunction "1_1") (pintype "passive"))
      (node (ref "U3") (pin "27") (pinfunction "PB1_27") (pintype "bidirectional"))
    )
    (net (code "33") (name "PB6") (class "Default")
      (node (ref "U1") (pin "2") (pinfunction "INPUT_1_2") (pintype "input"))
      (node (ref "U3") (pin "58") (pinfunction "PB6_58") (pintype "bidirectional"))
    )
    (net (code "34") (name "PB7") (class "Default")
      (node (ref "U1") (pin "9") (pinfunction "INPUT_2_9") (pintype "input"))
      (node (ref "U3") (pin "59") (pinfunction "PB7_59") (pintype "bidirectional"))
    )
    (net (code "35") (name "PB8") (class "Default")
      (node (ref "U1") (pin "19") (pinfunction "INPUT_4_19") (pintype "input"))
      (node (ref "U3") (pin "61") (pinfunction "PB8_61") (pintype "bidirectional"))
    )
    (net (code "36") (name "PB9") (class "Default")
      (node (ref "U1") (pin "12") (pinfunction "INPUT_3_12") (pintype "input"))
      (node (ref "U3") (pin "62") (pinfunction "PB9_62") (pintype "bidirectional"))
    )
    (net (code "37") (name "PB10") (class "Default")
      (node (ref "J4") (pin "3") (pinfunction "3_3") (pintype "passive"))
      (node (ref "U3") (pin "29") (pinfunction "PB10_29") (pintype "bidirectional"))
    )
    (net (code "38") (name "PB11") (class "Default")
      (node (ref "J4") (pin "4") (pinfunction "4_4") (pintype "passive"))
      (node (ref "U3") (pin "30") (pinfunction "PB11_30") (pintype "bidirectional"))
    )
    (net (code "39") (name "PB13") (class "Default")
      (node (ref "R2D") (pin "1") (pinfunction "1_1") (pintype "passive"))
      (node (ref "U3") (pin "34") (pinfunction "PB13_34") (pintype "bidirectional"))
    )
    (net (code "40") (name "PC4") (class "Default")
      (node (ref "Q1D") (pin "1") (pinfunction "E_1") (pintype "passive"))
      (node (ref "R1D") (pin "1") (pinfunction "1_1") (pintype "passive"))
      (node (ref "U3") (pin "24") (pinfunction "PC4_24") (pintype "bidirectional"))
    )
    (net (code "41") (name "PC5") (class "Default")
      (node (ref "Q1A") (pin "1") (pinfunction "E_1") (pintype "passive"))
      (node (ref "R1A") (pin "1") (pinfunction "1_1") (pintype "passive"))
      (node (ref "U3") (pin "25") (pinfunction "PC5_25") (pintype "bidirectional"))
    )
    (net (code "42") (name "PC7") (class "Default")
      (node (ref "Q1C") (pin "1") (pinfunction "E_1") (pintype "passive"))
      (node (ref "R1C") (pin "1") (pinfunction "1_1") (pintype "passive"))
      (node (ref "U3") (pin "38") (pinfunction "PC7_38") (pintype "bidirectional"))
    )
    (net (code "43") (name "PC9") (class "Default")
      (node (ref "R2A") (pin "1") (pinfunction "1_1") (pintype "passive"))
      (node (ref "U3") (pin "40") (pinfunction "PC9_40") (pintype "bidirectional"))
    )
    (net (code "44") (name "SWCLK") (class "Default")
      (node (ref "J3") (pin "1") (pinfunction "1_1") (pintype "passive"))
      (node (ref "U3") (pin "49") (pinfunction "PA14_49") (pintype "bidirectional"))
    )
    (net (code "45") (name "SWDIO") (class "Default")
      (node (ref "J3") (pin "3") (pinfunction "3_3") (pintype "passive"))
      (node (ref "U3") (pin "46") (pinfunction "PA13_46") (pintype "bidirectional"))
    )
    (net (code "46") (name "VBAT") (class "Default")
      (node (ref "C3") (pin "2") (pinfunction "2_2") (pintype "passive"))
      (node (ref "C4") (pin "2") (pinfunction "2_2") (pintype "passive"))
      (node (ref "C5") (pin "1") (pinfunction "1_1") (pintype "passive"))
      (node (ref "C6") (pin "2") (pinfunction "2_2") (pintype "passive"))
      (node (ref "S1") (pin "3") (pinfunction "3_3") (pintype "passive"))
      (node (ref "U1") (pin "10") (pinfunction "VS_10") (pintype "power_in"))
      (node (ref "U1") (pin "20") (pinfunction "VSS_20") (pintype "power_in"))
      (node (ref "U2") (pin "4") (pinfunction "VIN_4") (pintype "input"))
    )
    (net (code "47") (name "VCC") (class "Default")
      (node (ref "C13") (pin "2") (pinfunction "2_2") (pintype "passive"))
      (node (ref "C14") (pin "2") (pinfunction "2_2") (pintype "passive"))
      (node (ref "C15") (pin "2") (pinfunction "2_2") (pintype "passive"))
      (node (ref "C16") (pin "1") (pinfunction "1_1") (pintype "passive"))
      (node (ref "C17") (pin "1") (pinfunction "1_1") (pintype "passive"))
      (node (ref "C18") (pin "1") (pinfunction "1_1") (pintype "passive"))
      (node (ref "C19\\") (pin "1") (pinfunction "1_1") (pintype "passive"))
      (node (ref "C2") (pin "2") (pinfunction "2_2") (pintype "passive"))
      (node (ref "C20") (pin "1") (pinfunction "1_1") (pintype "passive"))
      (node (ref "C7A") (pin "1") (pinfunction "1_1") (pintype "passive"))
      (node (ref "C7B") (pin "1") (pinfunction "1_1") (pintype "passive"))
      (node (ref "C7C") (pin "1") (pinfunction "1_1") (pintype "passive"))
      (node (ref "C7D") (pin "1") (pinfunction "1_1") (pintype "passive"))
      (node (ref "C8A") (pin "2") (pinfunction "2_2") (pintype "passive"))
      (node (ref "C8B") (pin "2") (pinfunction "2_2") (pintype "passive"))
      (node (ref "C8C") (pin "2") (pinfunction "2_2") (pintype "passive"))
      (node (ref "C8D") (pin "2") (pinfunction "2_2") (pintype "passive"))
      (node (ref "J4") (pin "1") (pinfunction "1_1") (pintype "passive"))
      (node (ref "LEFT") (pin "3") (pinfunction "3_3") (pintype "passive"))
      (node (ref "Q1A") (pin "2") (pinfunction "C_2") (pintype "passive"))
      (node (ref "Q1B") (pin "2") (pinfunction "C_2") (pintype "passive"))
      (node (ref "Q1C") (pin "2") (pinfunction "C_2") (pintype "passive"))
      (node (ref "Q1D") (pin "2") (pinfunction "C_2") (pintype "passive"))
      (node (ref "R4A") (pin "2") (pinfunction "2_2") (pintype "passive"))
      (node (ref "R4B") (pin "2") (pinfunction "2_2") (pintype "passive"))
      (node (ref "R4C") (pin "2") (pinfunction "2_2") (pintype "passive"))
      (node (ref "R4D") (pin "2") (pinfunction "2_2") (pintype "passive"))
      (node (ref "RIGHT") (pin "3") (pinfunction "3_3") (pintype "passive"))
      (node (ref "U1") (pin "1") (pinfunction "ENABLE_1_1") (pintype "input"))
      (node (ref "U1") (pin "11") (pinfunction "ENABLE_2_11") (pintype "input"))
      (node (ref "U2") (pin "2") (pinfunction "VOUT_2") (pintype "output"))
      (node (ref "U2") (pin "3") (pinfunction "VOUT_3") (pintype "output"))
      (node (ref "U2") (pin "6") (pinfunction "VOUT_6") (pintype "output"))
      (node (ref "U2") (pin "7") (pinfunction "VOUT_7") (pintype "output"))
      (node (ref "U3") (pin "1") (pinfunction "VBAT_1") (pintype "power_in"))
      (node (ref "U3") (pin "13") (pinfunction "VDDA_13") (pintype "power_in"))
      (node (ref "U3") (pin "19") (pinfunction "VDD_2_19") (pintype "power_in"))
      (node (ref "U3") (pin "32") (pinfunction "VDD_3_32") (pintype "power_in"))
      (node (ref "U3") (pin "48") (pinfunction "VDD_4_48") (pintype "power_in"))
      (node (ref "U3") (pin "64") (pinfunction "VDD_64") (pintype "power_in"))
    )
    (net (code "48") (name "unconnected-(J4-Pad5)") (class "Default")
      (node (ref "J4") (pin "5") (pinfunction "5_5") (pintype "passive"))
    )
    (net (code "49") (name "unconnected-(J4-Pad6)") (class "Default")
      (node (ref "J4") (pin "6") (pinfunction "6_6") (pintype "passive"))
    )
    (net (code "50") (name "unconnected-(J4-Pad7)") (class "Default")
      (node (ref "J4") (pin "7") (pinfunction "7_7") (pintype "passive"))
    )
    (net (code "51") (name "unconnected-(J4-Pad8)") (class "Default")
      (node (ref "J4") (pin "8") (pinfunction "8_8") (pintype "passive"))
    )
    (net (code "52") (name "unconnected-(S1-Pad1)") (class "Default")
      (node (ref "S1") (pin "1") (pinfunction "1_1") (pintype "passive"))
    )
    (net (code "53") (name "unconnected-(U3A-PA2-Pad16)") (class "Default")
      (node (ref "U3") (pin "16") (pinfunction "PA2_16") (pintype "bidirectional"))
    )
    (net (code "54") (name "unconnected-(U3A-PA3-Pad17)") (class "Default")
      (node (ref "U3") (pin "17") (pinfunction "PA3_17") (pintype "bidirectional"))
    )
    (net (code "55") (name "unconnected-(U3A-PA4-Pad20)") (class "Default")
      (node (ref "U3") (pin "20") (pinfunction "PA4_20") (pintype "bidirectional"))
    )
    (net (code "56") (name "unconnected-(U3A-PA5-Pad21)") (class "Default")
      (node (ref "U3") (pin "21") (pinfunction "PA5_21") (pintype "bidirectional"))
    )
    (net (code "57") (name "unconnected-(U3A-PA10-Pad43)") (class "Default")
      (node (ref "U3") (pin "43") (pinfunction "PA10_43") (pintype "bidirectional"))
    )
    (net (code "58") (name "unconnected-(U3A-PA11-Pad44)") (class "Default")
      (node (ref "U3") (pin "44") (pinfunction "PA11_44") (pintype "bidirectional"))
    )
    (net (code "59") (name "unconnected-(U3A-PA12-Pad45)") (class "Default")
      (node (ref "U3") (pin "45") (pinfunction "PA12_45") (pintype "bidirectional"))
    )
    (net (code "60") (name "unconnected-(U3A-PA15-Pad50)") (class "Default")
      (node (ref "U3") (pin "50") (pinfunction "PA15_50") (pintype "bidirectional"))
    )
    (net (code "61") (name "unconnected-(U3A-PB0-Pad26)") (class "Default")
      (node (ref "U3") (pin "26") (pinfunction "PB0_26") (pintype "bidirectional"))
    )
    (net (code "62") (name "unconnected-(U3A-PB3-Pad55)") (class "Default")
      (node (ref "U3") (pin "55") (pinfunction "PB3_55") (pintype "bidirectional"))
    )
    (net (code "63") (name "unconnected-(U3A-PB4-Pad56)") (class "Default")
      (node (ref "U3") (pin "56") (pinfunction "PB4_56") (pintype "bidirectional"))
    )
    (net (code "64") (name "unconnected-(U3A-PB5-Pad57)") (class "Default")
      (node (ref "U3") (pin "57") (pinfunction "PB5_57") (pintype "bidirectional"))
    )
    (net (code "65") (name "unconnected-(U3A-PB12-Pad33)") (class "Default")
      (node (ref "U3") (pin "33") (pinfunction "PB12_33") (pintype "bidirectional"))
    )
    (net (code "66") (name "unconnected-(U3A-PB14-Pad35)") (class "Default")
      (node (ref "U3") (pin "35") (pinfunction "PB14_35") (pintype "bidirectional"))
    )
    (net (code "67") (name "unconnected-(U3A-PB15-Pad36)") (class "Default")
      (node (ref "U3") (pin "36") (pinfunction "PB15_36") (pintype "bidirectional"))
    )
    (net (code "68") (name "unconnected-(U3A-PC0-Pad8)") (class "Default")
      (node (ref "U3") (pin "8") (pinfunction "PC0_8") (pintype "bidirectional"))
    )
    (net (code "69") (name "unconnected-(U3A-PC1-Pad9)") (class "Default")
      (node (ref "U3") (pin "9") (pinfunction "PC1_9") (pintype "bidirectional"))
    )
    (net (code "70") (name "unconnected-(U3A-PC2-Pad10)") (class "Default")
      (node (ref "U3") (pin "10") (pinfunction "PC2_10") (pintype "bidirectional"))
    )
    (net (code "71") (name "unconnected-(U3A-PC3-Pad11)") (class "Default")
      (node (ref "U3") (pin "11") (pinfunction "PC3_11") (pintype "bidirectional"))
    )
    (net (code "72") (name "unconnected-(U3A-PC6-Pad37)") (class "Default")
      (node (ref "U3") (pin "37") (pinfunction "PC6_37") (pintype "bidirectional"))
    )
    (net (code "73") (name "unconnected-(U3A-PC8-Pad39)") (class "Default")
      (node (ref "U3") (pin "39") (pinfunction "PC8_39") (pintype "bidirectional"))
    )
    (net (code "74") (name "unconnected-(U3A-PC10-Pad51)") (class "Default")
      (node (ref "U3") (pin "51") (pinfunction "PC10_51") (pintype "bidirectional"))
    )
    (net (code "75") (name "unconnected-(U3A-PC11-Pad52)") (class "Default")
      (node (ref "U3") (pin "52") (pinfunction "PC11_52") (pintype "bidirectional"))
    )
    (net (code "76") (name "unconnected-(U3A-PC12-Pad53)") (class "Default")
      (node (ref "U3") (pin "53") (pinfunction "PC12_53") (pintype "bidirectional"))
    )
    (net (code "77") (name "unconnected-(U3A-PC13-Pad2)") (class "Default")
      (node (ref "U3") (pin "2") (pinfunction "PC13_2") (pintype "bidirectional"))
    )
    (net (code "78") (name "unconnected-(U3A-PC14{slash}OSC32_IN-Pad3)") (class "Default")
      (node (ref "U3") (pin "3") (pinfunction "PC14/OSC32_IN_3") (pintype "bidirectional"))
    )
    (net (code "79") (name "unconnected-(U3A-PC15-OSC32_OUT-Pad4)") (class "Default")
      (node (ref "U3") (pin "4") (pinfunction "PC15-OSC32_OUT_4") (pintype "bidirectional"))
    )
    (net (code "80") (name "unconnected-(U3A-PD2-Pad54)") (class "Default")
      (node (ref "U3") (pin "54") (pinfunction "PD2_54") (pintype "bidirectional"))
    )
    (net (code "81") (name "unconnected-(U3A-PH0{slash}OSC_IN-Pad5)") (class "Default")
      (node (ref "U3") (pin "5") (pinfunction "PH0/OSC_IN_5") (pintype "bidirectional"))
    )
    (net (code "82") (name "unconnected-(U3A-PH1{slash}OSC_OUT-Pad6)") (class "Default")
      (node (ref "U3") (pin "6") (pinfunction "PH1/OSC_OUT_6") (pintype "bidirectional"))
    )
  )
)
